# RF_LoRa___GPS.net
KiCad netlist of a schematic drawn in Altium Designer
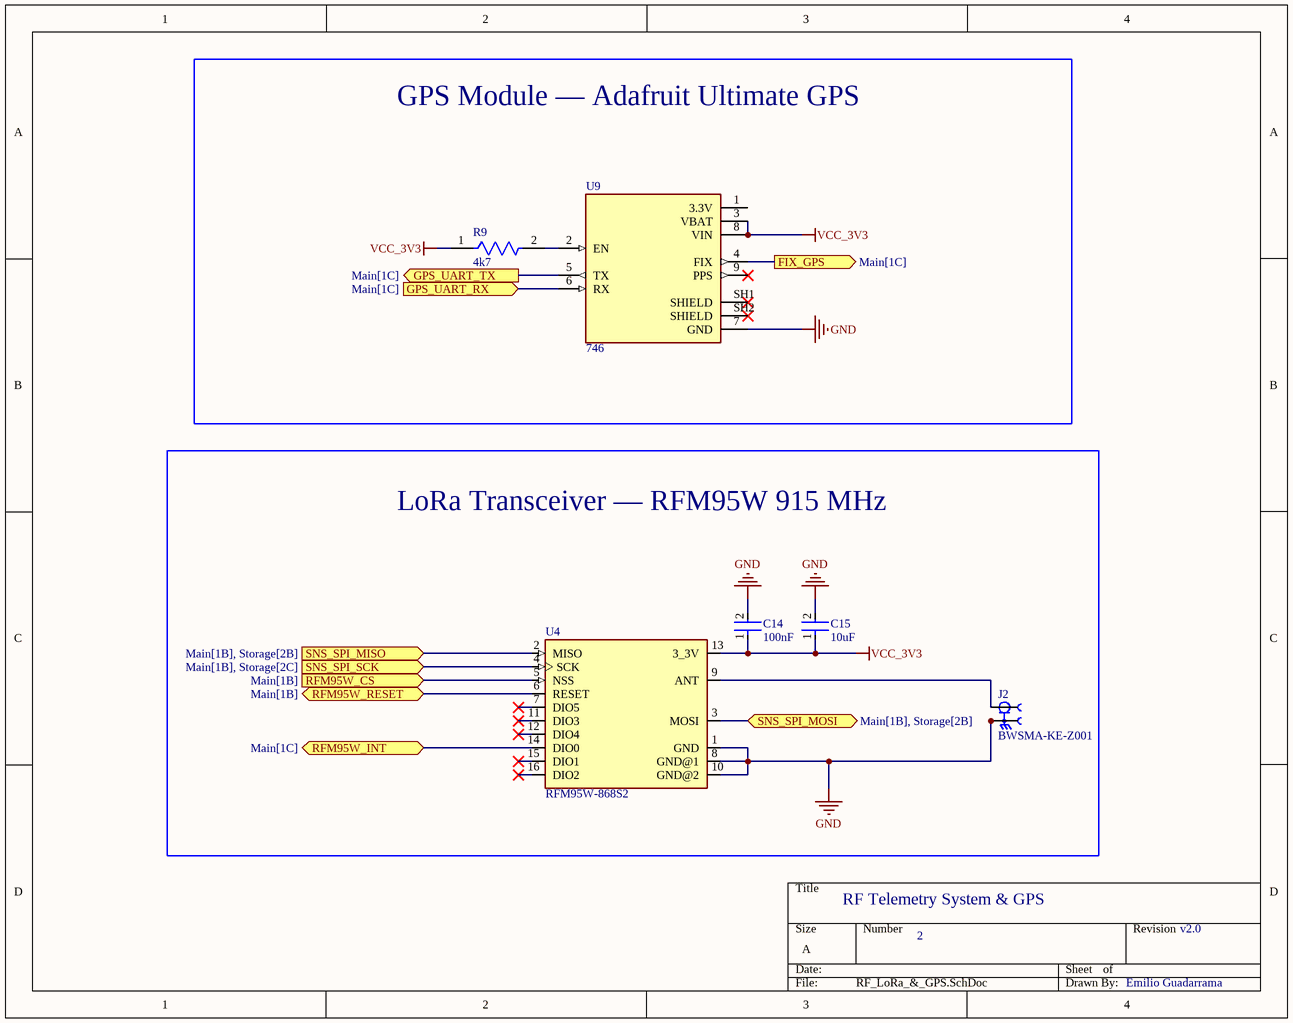
[diagram p0: RF_LoRa_&_GPS.SchDoc]

(export (version "E")
  (design (tool "Eeschema 10.0.6"))
  (components
    (comp (ref "C14")
      (value "100nF")
      (footprint "FP-C0805C-DN-MFG")
      (description "CAP CER 0.1UF 50V X7R 0805")
      (fields
        (field (name "MANUFACTURER PART NUMBER") "C0805C104K5RACTU")
        (field (name "MANUFACTURER") "KEMET")
      )
      (libsource (lib "Altium Content Vault") (part "b4654b650e69147ec39a6b967a45e02"))
    )
    (comp (ref "C15")
      (value "10uF")
      (footprint "FP-C0805C-DN-MFG")
      (description "CAP CER 0.1UF 50V X7R 0805")
      (fields
        (field (name "MANUFACTURER PART NUMBER") "C0805C104K5RACTU")
        (field (name "MANUFACTURER") "KEMET")
      )
      (libsource (lib "Altium Content Vault") (part "b4654b650e69147ec39a6b967a45e02"))
    )
    (comp (ref "J2")
      (value "BWSMA-KE-Z001")
      (footprint "BAT_WIRELESS_BWSMA-KE-Z001")
      (fields (field (name "MF") "Bat Wireless"))
      (libsource (lib "SMA") (part "BWSMA-KE-Z001"))
    )
    (comp (ref "R9")
      (value "4k7")
      (footprint "FP-MCT0603-IPC_A")
      (description "RES SMD 100 OHM 1% 1/8W 0603")
      (fields (field (name "TOLERANCE") "0.1%"))
      (libsource (lib "Altium Content Vault") (part "1029c3af85768c4190bb7ad29bc67b5"))
    )
    (comp (ref "U4")
      (value "RFM95W-868S2")
      (footprint "XCVR_RFM95W-868S2")
      (description "General ISM < 1GHz LoRaâ„¢ Transceiver Module 868MHz Antenna Not Included Surface Mount")
      (fields (field (name "MF") "RF"))
      (libsource (lib "Antenna-RFM95W-868S2") (part "RFM95W-868S2"))
    )
    (comp (ref "U9")
      (value "746")
      (footprint "XCVR_746")
      (fields (field (name "MF") "Adafruit Industries"))
      (libsource (lib "GPS") (part "746"))
    )
  )
  (nets
    (net (code "1") (name "/FIX_GPS") (class "Default")
      (node (ref "U9") (pin "4") (pinfunction "FIX_4") (pintype "output"))
    )
    (net (code "2") (name "/GPS_UART_RX") (class "Default")
      (node (ref "U9") (pin "6") (pinfunction "RX_6") (pintype "input"))
    )
    (net (code "3") (name "/GPS_UART_TX") (class "Default")
      (node (ref "U9") (pin "5") (pinfunction "TX_5") (pintype "output"))
    )
    (net (code "4") (name "/RFM95W_CS") (class "Default")
      (node (ref "U4") (pin "5") (pinfunction "NSS_5") (pintype "input"))
    )
    (net (code "5") (name "/RFM95W_INT") (class "Default")
      (node (ref "U4") (pin "14") (pinfunction "DIO0_14") (pintype "bidirectional"))
    )
    (net (code "6") (name "/RFM95W_RESET") (class "Default")
      (node (ref "U4") (pin "6") (pinfunction "RESET_6") (pintype "bidirectional"))
    )
    (net (code "7") (name "/SNS_SPI_MISO") (class "Default")
      (node (ref "U4") (pin "2") (pinfunction "MISO_2") (pintype "input"))
    )
    (net (code "8") (name "/SNS_SPI_MOSI") (class "Default")
      (node (ref "U4") (pin "3") (pinfunction "MOSI_3") (pintype "bidirectional"))
    )
    (net (code "9") (name "/SNS_SPI_SCK") (class "Default")
      (node (ref "U4") (pin "4") (pinfunction "SCK_4") (pintype "input"))
    )
    (net (code "10") (name "GND") (class "Default")
      (node (ref "C14") (pin "2") (pinfunction "2_2") (pintype "passive"))
      (node (ref "C15") (pin "2") (pinfunction "2_2") (pintype "passive"))
      (node (ref "J2") (pin "2_1") (pinfunction "2_2_1") (pintype "passive"))
      (node (ref "J2") (pin "2_2") (pinfunction "2_2_2") (pintype "passive"))
      (node (ref "J2") (pin "2_3") (pinfunction "2_2_3") (pintype "passive"))
      (node (ref "J2") (pin "2_4") (pinfunction "2_2_4") (pintype "passive"))
      (node (ref "U4") (pin "1") (pinfunction "GND_1") (pintype "power_in"))
      (node (ref "U4") (pin "10") (pinfunction "GND@2_10") (pintype "power_in"))
      (node (ref "U4") (pin "8") (pinfunction "GND@1_8") (pintype "power_in"))
      (node (ref "U9") (pin "7") (pinfunction "GND_7") (pintype "power_in"))
    )
    (net (code "11") (name "Net-(U4-ANT)") (class "Default")
      (node (ref "J2") (pin "1") (pinfunction "1_1") (pintype "passive"))
      (node (ref "U4") (pin "9") (pinfunction "ANT_9") (pintype "passive"))
    )
    (net (code "12") (name "Net-(U9-EN)") (class "Default")
      (node (ref "R9") (pin "2") (pinfunction "2_2") (pintype "passive"))
      (node (ref "U9") (pin "2") (pinfunction "EN_2") (pintype "input"))
    )
    (net (code "13") (name "VCC_3V3") (class "Default")
      (node (ref "C14") (pin "1") (pinfunction "1_1") (pintype "passive"))
      (node (ref "C15") (pin "1") (pinfunction "1_1") (pintype "passive"))
      (node (ref "R9") (pin "1") (pinfunction "1_1") (pintype "passive"))
      (node (ref "U4") (pin "13") (pinfunction "3_3V_13") (pintype "power_in"))
      (node (ref "U9") (pin "3") (pinfunction "VBAT_3") (pintype "power_in"))
      (node (ref "U9") (pin "8") (pinfunction "VIN_8") (pintype "power_in"))
    )
    (net (code "14") (name "unconnected-(U4-DIO1-Pad15)") (class "Default")
      (node (ref "U4") (pin "15") (pinfunction "DIO1_15") (pintype "bidirectional+no_connect"))
    )
    (net (code "15") (name "unconnected-(U4-DIO2-Pad16)") (class "Default")
      (node (ref "U4") (pin "16") (pinfunction "DIO2_16") (pintype "bidirectional+no_connect"))
    )
    (net (code "16") (name "unconnected-(U4-DIO3-Pad11)") (class "Default")
      (node (ref "U4") (pin "11") (pinfunction "DIO3_11") (pintype "bidirectional+no_connect"))
    )
    (net (code "17") (name "unconnected-(U4-DIO4-Pad12)") (class "Default")
      (node (ref "U4") (pin "12") (pinfunction "DIO4_12") (pintype "bidirectional+no_connect"))
    )
    (net (code "18") (name "unconnected-(U4-DIO5-Pad7)") (class "Default")
      (node (ref "U4") (pin "7") (pinfunction "DIO5_7") (pintype "bidirectional+no_connect"))
    )
    (net (code "19") (name "unconnected-(U9-3.3V-Pad1)") (class "Default")
      (node (ref "U9") (pin "1") (pinfunction "3.3V_1") (pintype "power_in"))
    )
    (net (code "20") (name "unconnected-(U9-PPS-Pad9)") (class "Default")
      (node (ref "U9") (pin "9") (pinfunction "PPS_9") (pintype "output+no_connect"))
    )
    (net (code "21") (name "unconnected-(U9-SHIELD-PadSH1)") (class "Default")
      (node (ref "U9") (pin "SH1") (pinfunction "SHIELD_SH1") (pintype "passive+no_connect"))
    )
    (net (code "22") (name "unconnected-(U9-SHIELD-PadSH2)") (class "Default")
      (node (ref "U9") (pin "SH2") (pinfunction "SHIELD_SH2") (pintype "passive+no_connect"))
    )
  )
)
